# weaver_bicolor.net
KiCad netlist of a schematic drawn in EAGLE
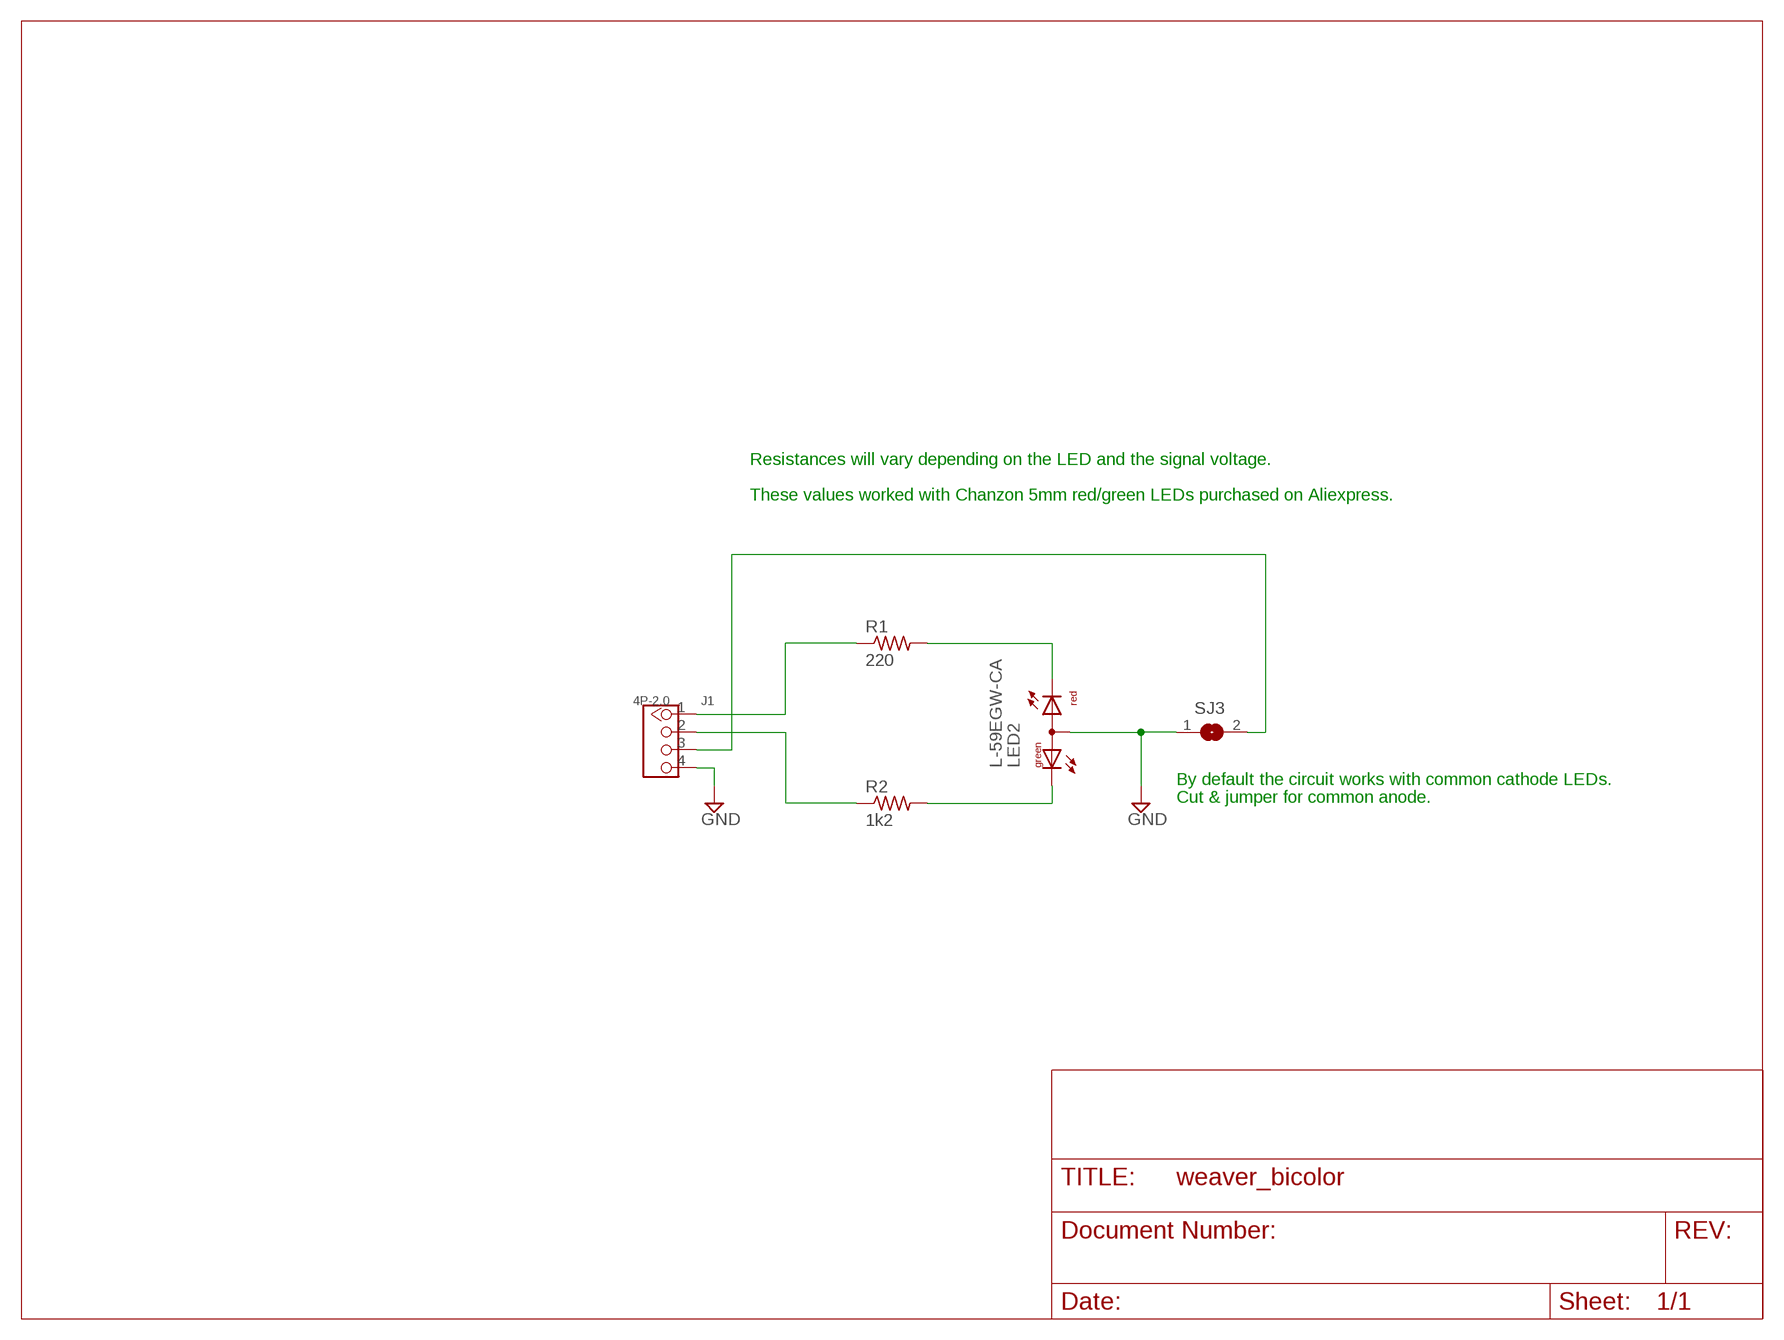
[diagram p0: schematic, sheet 1]

(export (version "E")
  (design (tool "Eeschema 10.0.6"))
  (components
    (comp (ref "J1")
      (value "4P-2.0")
      (footprint "eagle-import:HW4-2.0")
      (libsource (lib "eagle-import") (part "GROVE-CONNECTOR-DIP(4P-2.0)"))
    )
    (comp (ref "LED2")
      (value "L-59EGW-CA")
      (footprint "eagle-import:L-59EGW-CA")
      (libsource (lib "eagle-import") (part "L-59EGW-CA"))
    )
    (comp (ref "R1")
      (value "220")
      (footprint "eagle-import:R0805")
      (libsource (lib "eagle-import") (part "R-US_R0805"))
    )
    (comp (ref "R2")
      (value "1k2")
      (footprint "eagle-import:R0805")
      (libsource (lib "eagle-import") (part "R-US_R0805"))
    )
    (comp (ref "SJ3") (value "SJ") (footprint "eagle-import:SJ") (libsource (lib "eagle-import") (part "SJ")))
  )
  (nets
    (net (code "1") (name "GND") (class "Default")
      (node (ref "J1") (pin "4") (pinfunction "4_4") (pintype "bidirectional"))
      (node (ref "LED2") (pin "2") (pinfunction "A_2") (pintype "passive"))
      (node (ref "SJ3") (pin "1") (pinfunction "1_1") (pintype "passive"))
    )
    (net (code "2") (name "Net-(J1-Pad1)") (class "Default")
      (node (ref "J1") (pin "1") (pinfunction "1_1") (pintype "bidirectional"))
      (node (ref "R1") (pin "1") (pinfunction "1_1") (pintype "passive"))
    )
    (net (code "3") (name "Net-(J1-Pad2)") (class "Default")
      (node (ref "J1") (pin "2") (pinfunction "2_2") (pintype "bidirectional"))
      (node (ref "R2") (pin "1") (pinfunction "1_1") (pintype "passive"))
    )
    (net (code "4") (name "Net-(J1-Pad3)") (class "Default")
      (node (ref "J1") (pin "3") (pinfunction "3_3") (pintype "bidirectional"))
      (node (ref "SJ3") (pin "2") (pinfunction "2_2") (pintype "passive"))
    )
    (net (code "5") (name "Net-(LED2-CG)") (class "Default")
      (node (ref "LED2") (pin "3") (pinfunction "CG_3") (pintype "passive"))
      (node (ref "R2") (pin "2") (pinfunction "2_2") (pintype "passive"))
    )
    (net (code "6") (name "Net-(LED2-CR)") (class "Default")
      (node (ref "LED2") (pin "1") (pinfunction "CR_1") (pintype "passive"))
      (node (ref "R1") (pin "2") (pinfunction "2_2") (pintype "passive"))
    )
  )
)
